# dcdc_60v_12v.net
KiCad netlist of a schematic drawn in Altium Designer
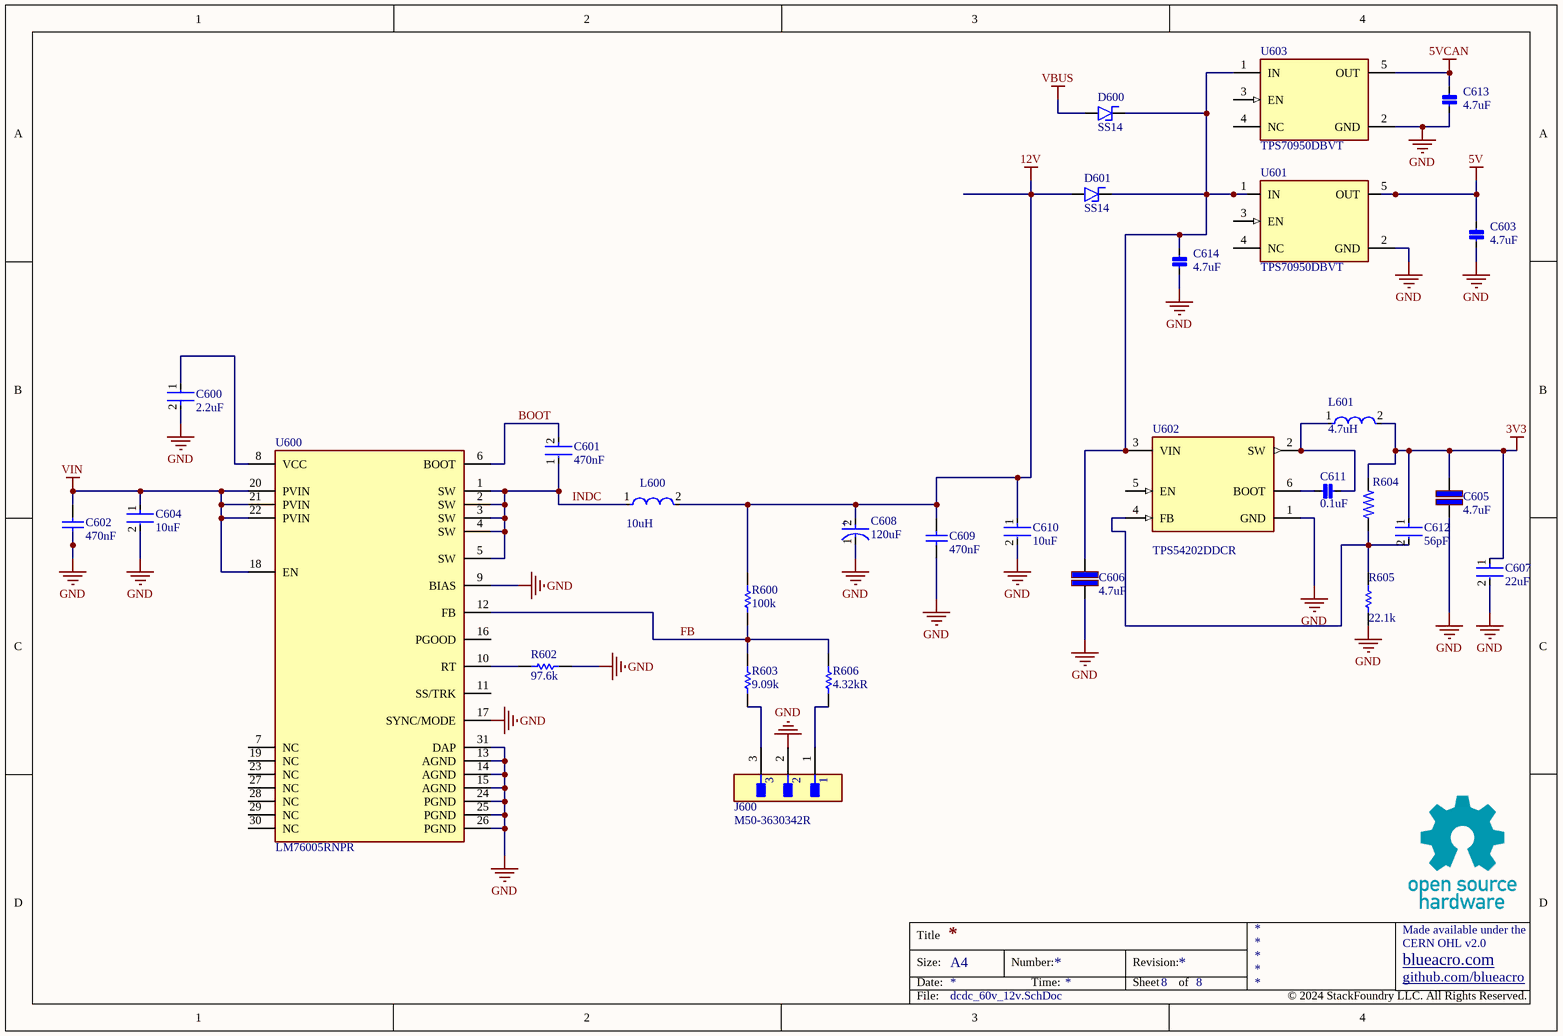
[diagram p0: dcdc_60v_12v.SchDoc]

(export (version "E")
  (design (tool "Eeschema 10.0.6"))
  (components
    (comp (ref "C600")
      (value "2.2uF")
      (footprint "FP-C1608-080-0_1-IPC_A")
      (description "Cap Ceramic 2.2uF 16V X6S 10% Pad SMD 0603 105°C Low ESR T/R")
      (fields (field (name "TOLERANCE") "10%") (field (name "Comment") "CAP 2.2uF 0603 16V X6S"))
      (libsource (lib "StackFoundry LLC") (part "236180d848d6139a670b325ea6854c9"))
    )
    (comp (ref "C601")
      (value "470nF")
      (footprint "FP-C1608-080-0_1-IPC_A")
      (description "Multilayer Ceramic Capacitor, 0.47 uF, 50 V, ± 10%, X7R, 0603 [1608 Metric]")
      (fields (field (name "TOLERANCE") "10%") (field (name "VOLTAGE") "50V"))
      (libsource (lib "StackFoundry LLC") (part "236180d848d6139a670b325ea6854c9"))
    )
    (comp (ref "C602")
      (value "470nF")
      (footprint "CAPC1210(3225)230_M")
      (description "Multilayer Ceramic Capacitor, 0.47 uF, 50 V, ± 10%, X7R, 1210 [3225 Metric]")
      (fields (field (name "TOLERANCE") "10%") (field (name "VOLTAGE") "50V"))
      (libsource (lib "StackFoundry LLC") (part "CAP"))
    )
    (comp (ref "C603")
      (value "4.7uF")
      (footprint "FP-CL10-IPC_C")
      (description "Cap Ceramic 4.7uF 6.3V X7R 10% SMD 0603 125°C Paper T/R")
      (fields (field (name "Comment") "CAP 4.7uF 0603 6.3V X7R"))
      (libsource (lib "StackFoundry LLC") (part "C-EU"))
    )
    (comp (ref "C604")
      (value "10uF")
      (footprint "FP-GRM32E-0_2-0_3-MFG")
      (description "Multilayer Ceramic Capacitors MLCC - SMD/SMT 1210 10uF 63volts *Derate Voltage/Temp")
      (fields (field (name "TOLERANCE") "10%") (field (name "VOLTAGE") "63V"))
      (libsource (lib "StackFoundry LLC") (part "11868f565c42a9108669ba33697ecf6"))
    )
    (comp (ref "C605")
      (value "4.7uF")
      (footprint "CAPC3225X20N")
      (description "CAP CER 4.7UF 50V X7R 1210")
      (fields (field (name "VOLTAGE") "50V") (field (name "TOLERANCE") "10%"))
      (libsource (lib "StackFoundry LLC") (part "4.7uF"))
    )
    (comp (ref "C606")
      (value "4.7uF")
      (footprint "CAPC3225X20N")
      (description "CAP CER 4.7UF 50V X7R 1210")
      (fields (field (name "VOLTAGE") "50V") (field (name "TOLERANCE") "10%"))
      (libsource (lib "StackFoundry LLC") (part "4.7uF"))
    )
    (comp (ref "C607")
      (value "22uF")
      (footprint "FP-1210-L_3_2_0_3-W_2_5_0-MFG")
      (description "1210 22 uF 25 V ±20% Tolerance X7R Multilayer Ceramic Chip Capacitor")
      (fields (field (name "TOLERANCE") "20%") (field (name "Comment") "CAP 22uF 25V 1210 X7R"))
      (libsource (lib "StackFoundry LLC") (part "02cd4be3c70576c341d710602a673aa"))
    )
    (comp (ref "C608")
      (value "120uF")
      (footprint "FP-OS-CON-SMT-F12-MFG")
      (description "Cap Aluminum Polymer 120uF 35VDC 20%( 10 X 12.6mm) SMD 0.018 Ohm 4400mA 5000h 105C T/R")
      (fields (field (name "VOLTAGE") "35V") (field (name "TOLERANCE") "20%"))
      (libsource (lib "StackFoundry LLC") (part "a7907c86e72a156c28511143de7831b"))
    )
    (comp (ref "C609")
      (value "470nF")
      (footprint "CAPC1210(3225)230_M")
      (description "Multilayer Ceramic Capacitor, 0.47 uF, 50 V, ± 10%, X7R, 1210 [3225 Metric]")
      (fields (field (name "TOLERANCE") "10%") (field (name "VOLTAGE") "50V"))
      (libsource (lib "StackFoundry LLC") (part "CAP"))
    )
    (comp (ref "C610")
      (value "10uF")
      (footprint "FP-GRM32E-0_2-0_3-MFG")
      (description "Multilayer Ceramic Capacitors MLCC - SMD/SMT 1210 10uF 63volts *Derate Voltage/Temp")
      (fields (field (name "TOLERANCE") "10%") (field (name "VOLTAGE") "63V"))
      (libsource (lib "StackFoundry LLC") (part "11868f565c42a9108669ba33697ecf6"))
    )
    (comp (ref "C611")
      (value "0.1uF")
      (footprint "FP-CL10-IPC_B")
      (description "Cap Ceramic 0.1uF 50V X7R 20% SMD 0603 125C Paper T/R")
      (fields (field (name "VOLTAGE") "50V") (field (name "Comment") "CAP 0.1uF 50V X7R 0603"))
      (libsource (lib "") (part "C-EU_1"))
    )
    (comp (ref "C612")
      (value "56pF")
      (footprint "FP-C0603C-CF-IPC_B")
      (description "Multilayer Ceramic Capacitor, 56 pF, 50 V, ± 5%, C0G (NP0), 0603 [1608 Metric]")
      (fields (field (name "TOLERANCE") "5%") (field (name "Comment") "C0603C560J5GACTU"))
      (libsource (lib "StackFoundry LLC") (part "b4654b650e69147ec39a6b967a45e02"))
    )
    (comp (ref "C613")
      (value "4.7uF")
      (footprint "FP-CL10-IPC_C")
      (description "Cap Ceramic 4.7uF 6.3V X7R 10% SMD 0603 125°C Paper T/R")
      (fields (field (name "Comment") "CAP 4.7uF 0603 6.3V X7R"))
      (libsource (lib "StackFoundry LLC") (part "C-EU"))
    )
    (comp (ref "C614")
      (value "4.7uF")
      (footprint "FP-CL10-IPC_C")
      (description "Cap Ceramic 4.7uF 6.3V X7R 10% SMD 0603 125°C Paper T/R")
      (fields (field (name "Comment") "CAP 4.7uF 0603 6.3V X7R"))
      (libsource (lib "StackFoundry LLC") (part "C-EU"))
    )
    (comp (ref "D600")
      (value "SS14")
      (footprint "SMA")
      (libsource (lib "StackFoundry LLC") (part "DIODE_SCHOTTKY"))
    )
    (comp (ref "D601")
      (value "SS14")
      (footprint "SMA")
      (libsource (lib "StackFoundry LLC") (part "DIODE_SCHOTTKY"))
    )
    (comp (ref "J600")
      (value "M50-3630342R")
      (footprint "FP-M50-3630342R-MFG")
      (description "3 Pos. Male SIL Vertical SMT Conn. RoHS Compliant: Yes")
      (libsource (lib "StackFoundry LLC") (part "0d3f023dd272f625e17a2be33dea85f"))
    )
    (comp (ref "L600")
      (value "10uH")
      (footprint "FP-IHLP-5050FD-FP_2_945x4-MFG")
      (description "Inductor Power Shielded Wirewound 10uH 20% 100KHz Powdered Iron 10A 17.2mOhm DCR 5050 T/R")
      (fields (field (name "TOLERANCE") "20%") (field (name "Comment") "IHLP5050FDER100M01"))
      (libsource (lib "StackFoundry LLC") (part "725321dda6339637d4d059423bc1c3c"))
    )
    (comp (ref "L601")
      (value "4.7uH")
      (footprint "FP-SRN4018-MFG")
      (description "Ind Power Semi-Shielded Wirewound 4.7uH 20% 100KHz Ferrite 1.9A 1515 T/R")
      (fields (field (name "TOLERANCE") "20%") (field (name "Comment") "SRN4018-4R7M"))
      (libsource (lib "StackFoundry LLC") (part "725321dda6339637d4d059423bc1c3c"))
    )
    (comp (ref "R600")
      (value "100k")
      (footprint "RESC1608-IPC-LL")
      (description "SMD Chip Resistor, 100 kOhm, ± 1%, 100 mW, 0603 [1608 Metric], Thick Film, General Purpose")
      (fields (field (name "TOLERANCE") "1%") (field (name "Comment") "100k 0603 1%"))
      (libsource (lib "StackFoundry LLC") (part "RES"))
    )
    (comp (ref "R602")
      (value "97.6k")
      (footprint "RESC1608-IPC-LL")
      (description "Res Thick Film 0603 97.6K Ohm 1% 1/10W ±100ppm/°C Molded SMD Paper T/R")
      (fields (field (name "TOLERANCE") "1%") (field (name "Comment") "97.6k 0603 1%"))
      (libsource (lib "StackFoundry LLC") (part "RES"))
    )
    (comp (ref "R603")
      (value "9.09k")
      (footprint "RESC1608-IPC-LL")
      (description "SMD Chip Resistor, 9.09 kOhm, ± 1%, 100 mW, 0603 [1608 Metric], Thick Film, General Purpose")
      (fields (field (name "Comment") "9.09k 0603 1%"))
      (libsource (lib "StackFoundry LLC") (part "RES"))
    )
    (comp (ref "R604")
      (value "100k 0603 1%")
      (footprint "RESC1608-IPC-LL")
      (description "Res Thick Film 1.6 x 0.8 mm 100K Ohm 1% 0.1W(1/10W) 100ppm/ C Molded SMD Paper T/R")
      (libsource (lib "StackFoundry LLC") (part "R-US"))
    )
    (comp (ref "R605")
      (value "22.1k")
      (footprint "RESC1608-IPC-LL")
      (description "RES SMD 22.1KOHM 0.1% 1/10W 0603")
      (fields (field (name "Comment") "22.1k 0603 0.1%"))
      (libsource (lib "StackFoundry LLC") (part "RES"))
    )
    (comp (ref "R606")
      (value "4.32kR")
      (footprint "RESC1608X55X30LL15T15")
      (description "SMD Chip Resistor, 4.32 kOhm, ± 1%, 100 mW, 0603 [1608 Metric], Thick Film, Precision")
      (fields (field (name "TOLERANCE") "1%") (field (name "Comment") "4.32k 0603 1%"))
      (libsource (lib "StackFoundry LLC") (part "RES"))
    )
    (comp (ref "U600")
      (value "LM76005RNPR")
      (footprint "FP-RNP0030A-MFG")
      (description "3.5-V to 60-V, 5-A synchronous step-down voltage converter 30-WQFN -40 to 125")
      (libsource (lib "StackFoundry LLC") (part "e2228dfeb00daf3b479f14d7f837c1f"))
    )
    (comp (ref "U601")
      (value "TPS70950DBVT")
      (footprint "FP-DBV0005A-IPC_B")
      (description "IC REG LINEAR 5V 150MA SOT23-5 / 150-mA, 30-V, UltraLow IQ, Low-Dropout Regulators with Enable")
      (libsource (lib "StackFoundry LLC") (part "07e51adf658dd7550fcbd1980b41b01"))
    )
    (comp (ref "U602")
      (value "TPS54202DDCR")
      (footprint "FP-DDC0006A-IPC_C")
      (libsource (lib "StackFoundry LLC") (part "35c2d3f1afc239a386b2ba50eead654"))
    )
    (comp (ref "U603")
      (value "TPS70950DBVT")
      (footprint "FP-DBV0005A-IPC_B")
      (description "IC REG LINEAR 5V 150MA SOT23-5 / 150-mA, 30-V, UltraLow IQ, Low-Dropout Regulators with Enable")
      (libsource (lib "StackFoundry LLC") (part "07e51adf658dd7550fcbd1980b41b01"))
    )
  )
  (nets
    (net (code "1") (name "/BOOT") (class "Default")
      (node (ref "C601") (pin "2") (pinfunction "2_2") (pintype "passive"))
      (node (ref "U600") (pin "6") (pinfunction "BOOT_6") (pintype "power_in"))
    )
    (net (code "2") (name "/FB") (class "Default")
      (node (ref "R600") (pin "1") (pinfunction "1_1") (pintype "passive"))
      (node (ref "R603") (pin "2") (pinfunction "2_2") (pintype "passive"))
      (node (ref "R606") (pin "2") (pinfunction "2_2") (pintype "passive"))
      (node (ref "U600") (pin "12") (pinfunction "FB_12") (pintype "passive"))
    )
    (net (code "3") (name "/INDC") (class "Default")
      (node (ref "C601") (pin "1") (pinfunction "1_1") (pintype "passive"))
      (node (ref "L600") (pin "1") (pinfunction "1_1") (pintype "passive"))
      (node (ref "U600") (pin "1") (pinfunction "SW_1") (pintype "power_in"))
      (node (ref "U600") (pin "2") (pinfunction "SW_2") (pintype "power_in"))
      (node (ref "U600") (pin "3") (pinfunction "SW_3") (pintype "power_in"))
      (node (ref "U600") (pin "4") (pinfunction "SW_4") (pintype "power_in"))
      (node (ref "U600") (pin "5") (pinfunction "SW_5") (pintype "power_in"))
    )
    (net (code "4") (name "3V3") (class "Default")
      (node (ref "C605") (pin "2") (pintype "passive"))
      (node (ref "C607") (pin "1") (pinfunction "1_1") (pintype "passive"))
      (node (ref "C612") (pin "1") (pinfunction "1_1") (pintype "passive"))
      (node (ref "L601") (pin "2") (pinfunction "2_2") (pintype "passive"))
      (node (ref "R604") (pin "2") (pinfunction "2_2") (pintype "passive"))
    )
    (net (code "5") (name "5V") (class "Default")
      (node (ref "C603") (pin "1") (pinfunction "1_1") (pintype "passive"))
      (node (ref "U601") (pin "5") (pinfunction "OUT_5") (pintype "passive"))
    )
    (net (code "6") (name "5VCAN") (class "Default")
      (node (ref "C613") (pin "1") (pinfunction "1_1") (pintype "passive"))
      (node (ref "U603") (pin "5") (pinfunction "OUT_5") (pintype "passive"))
    )
    (net (code "7") (name "12V") (class "Default")
      (node (ref "C608") (pin "2") (pinfunction "A_2") (pintype "passive"))
      (node (ref "C609") (pin "2") (pinfunction "2_2") (pintype "passive"))
      (node (ref "C610") (pin "1") (pinfunction "1_1") (pintype "passive"))
      (node (ref "D601") (pin "A") (pinfunction "A_A") (pintype "power_in"))
      (node (ref "L600") (pin "2") (pinfunction "2_2") (pintype "passive"))
      (node (ref "R600") (pin "2") (pinfunction "2_2") (pintype "passive"))
    )
    (net (code "8") (name "GND") (class "Default")
      (node (ref "C600") (pin "2") (pinfunction "2_2") (pintype "passive"))
      (node (ref "C602") (pin "1") (pinfunction "1_1") (pintype "passive"))
      (node (ref "C603") (pin "2") (pinfunction "2_2") (pintype "passive"))
      (node (ref "C604") (pin "2") (pinfunction "2_2") (pintype "passive"))
      (node (ref "C605") (pin "1") (pintype "passive"))
      (node (ref "C606") (pin "1") (pintype "passive"))
      (node (ref "C607") (pin "2") (pinfunction "2_2") (pintype "passive"))
      (node (ref "C608") (pin "1") (pinfunction "C_1") (pintype "passive"))
      (node (ref "C609") (pin "1") (pinfunction "1_1") (pintype "passive"))
      (node (ref "C610") (pin "2") (pinfunction "2_2") (pintype "passive"))
      (node (ref "C613") (pin "2") (pinfunction "2_2") (pintype "passive"))
      (node (ref "C614") (pin "2") (pinfunction "2_2") (pintype "passive"))
      (node (ref "J600") (pin "2") (pinfunction "2_2") (pintype "passive"))
      (node (ref "R602") (pin "2") (pinfunction "2_2") (pintype "passive"))
      (node (ref "R605") (pin "1") (pinfunction "1_1") (pintype "passive"))
      (node (ref "U600") (pin "13") (pinfunction "AGND_13") (pintype "power_in"))
      (node (ref "U600") (pin "14") (pinfunction "AGND_14") (pintype "power_in"))
      (node (ref "U600") (pin "15") (pinfunction "AGND_15") (pintype "power_in"))
      (node (ref "U600") (pin "17") (pinfunction "SYNC/MODE_17") (pintype "passive"))
      (node (ref "U600") (pin "24") (pinfunction "PGND_24") (pintype "power_in"))
      (node (ref "U600") (pin "25") (pinfunction "PGND_25") (pintype "power_in"))
      (node (ref "U600") (pin "26") (pinfunction "PGND_26") (pintype "power_in"))
      (node (ref "U600") (pin "31") (pinfunction "DAP_31") (pintype "power_in"))
      (node (ref "U600") (pin "9") (pinfunction "BIAS_9") (pintype "power_in"))
      (node (ref "U601") (pin "2") (pinfunction "GND_2") (pintype "power_in"))
      (node (ref "U602") (pin "1") (pinfunction "GND_1") (pintype "power_in"))
      (node (ref "U603") (pin "2") (pinfunction "GND_2") (pintype "power_in"))
    )
    (net (code "9") (name "Net-(J600-Pad1)") (class "Default")
      (node (ref "J600") (pin "1") (pinfunction "1_1") (pintype "passive"))
      (node (ref "R606") (pin "1") (pinfunction "1_1") (pintype "passive"))
    )
    (net (code "10") (name "Net-(J600-Pad3)") (class "Default")
      (node (ref "J600") (pin "3") (pinfunction "3_3") (pintype "passive"))
      (node (ref "R603") (pin "1") (pinfunction "1_1") (pintype "passive"))
    )
    (net (code "11") (name "Net-(U600-RT)") (class "Default")
      (node (ref "R602") (pin "1") (pinfunction "1_1") (pintype "passive"))
      (node (ref "U600") (pin "10") (pinfunction "RT_10") (pintype "passive"))
    )
    (net (code "12") (name "Net-(U600-VCC)") (class "Default")
      (node (ref "C600") (pin "1") (pinfunction "1_1") (pintype "passive"))
      (node (ref "U600") (pin "8") (pinfunction "VCC_8") (pintype "power_in"))
    )
    (net (code "13") (name "Net-(U601-IN)") (class "Default")
      (node (ref "C606") (pin "2") (pintype "passive"))
      (node (ref "C614") (pin "1") (pinfunction "1_1") (pintype "passive"))
      (node (ref "D600") (pin "K") (pinfunction "K_K") (pintype "power_in"))
      (node (ref "D601") (pin "K") (pinfunction "K_K") (pintype "power_in"))
      (node (ref "U601") (pin "1") (pinfunction "IN_1") (pintype "power_in"))
      (node (ref "U602") (pin "3") (pinfunction "VIN_3") (pintype "power_in"))
      (node (ref "U603") (pin "1") (pinfunction "IN_1") (pintype "power_in"))
    )
    (net (code "14") (name "Net-(U602-BOOT)") (class "Default")
      (node (ref "C611") (pin "1") (pinfunction "1_1") (pintype "passive"))
      (node (ref "U602") (pin "6") (pinfunction "BOOT_6") (pintype "passive"))
    )
    (net (code "15") (name "Net-(U602-FB)") (class "Default")
      (node (ref "C612") (pin "2") (pinfunction "2_2") (pintype "passive"))
      (node (ref "R604") (pin "1") (pinfunction "1_1") (pintype "passive"))
      (node (ref "R605") (pin "2") (pinfunction "2_2") (pintype "passive"))
      (node (ref "U602") (pin "4") (pinfunction "FB_4") (pintype "input"))
    )
    (net (code "16") (name "Net-(U602-SW)") (class "Default")
      (node (ref "C611") (pin "2") (pinfunction "2_2") (pintype "passive"))
      (node (ref "L601") (pin "1") (pinfunction "1_1") (pintype "passive"))
      (node (ref "U602") (pin "2") (pinfunction "SW_2") (pintype "output"))
    )
    (net (code "17") (name "VBUS") (class "Default")
      (node (ref "D600") (pin "A") (pinfunction "A_A") (pintype "power_in"))
    )
    (net (code "18") (name "VIN") (class "Default")
      (node (ref "C602") (pin "2") (pinfunction "2_2") (pintype "passive"))
      (node (ref "C604") (pin "1") (pinfunction "1_1") (pintype "passive"))
      (node (ref "U600") (pin "18") (pinfunction "EN_18") (pintype "passive"))
      (node (ref "U600") (pin "20") (pinfunction "PVIN_20") (pintype "power_in"))
      (node (ref "U600") (pin "21") (pinfunction "PVIN_21") (pintype "power_in"))
      (node (ref "U600") (pin "22") (pinfunction "PVIN_22") (pintype "power_in"))
    )
    (net (code "19") (name "unconnected-(U600-NC-Pad7)") (class "Default")
      (node (ref "U600") (pin "7") (pinfunction "NC_7") (pintype "passive"))
    )
    (net (code "20") (name "unconnected-(U600-NC-Pad19)") (class "Default")
      (node (ref "U600") (pin "19") (pinfunction "NC_19") (pintype "passive"))
    )
    (net (code "21") (name "unconnected-(U600-NC-Pad23)") (class "Default")
      (node (ref "U600") (pin "23") (pinfunction "NC_23") (pintype "passive"))
    )
    (net (code "22") (name "unconnected-(U600-NC-Pad27)") (class "Default")
      (node (ref "U600") (pin "27") (pinfunction "NC_27") (pintype "passive"))
    )
    (net (code "23") (name "unconnected-(U600-NC-Pad28)") (class "Default")
      (node (ref "U600") (pin "28") (pinfunction "NC_28") (pintype "passive"))
    )
    (net (code "24") (name "unconnected-(U600-NC-Pad29)") (class "Default")
      (node (ref "U600") (pin "29") (pinfunction "NC_29") (pintype "passive"))
    )
    (net (code "25") (name "unconnected-(U600-NC-Pad30)") (class "Default")
      (node (ref "U600") (pin "30") (pinfunction "NC_30") (pintype "passive"))
    )
    (net (code "26") (name "unconnected-(U600-PGOOD-Pad16)") (class "Default")
      (node (ref "U600") (pin "16") (pinfunction "PGOOD_16") (pintype "open_collector"))
    )
    (net (code "27") (name "unconnected-(U600-SS{slash}TRK-Pad11)") (class "Default")
      (node (ref "U600") (pin "11") (pinfunction "SS/TRK_11") (pintype "passive"))
    )
    (net (code "28") (name "unconnected-(U601-EN-Pad3)") (class "Default")
      (node (ref "U601") (pin "3") (pinfunction "EN_3") (pintype "input"))
    )
    (net (code "29") (name "unconnected-(U601-NC-Pad4)") (class "Default")
      (node (ref "U601") (pin "4") (pinfunction "NC_4") (pintype "passive"))
    )
    (net (code "30") (name "unconnected-(U602-EN-Pad5)") (class "Default")
      (node (ref "U602") (pin "5") (pinfunction "EN_5") (pintype "input"))
    )
    (net (code "31") (name "unconnected-(U603-EN-Pad3)") (class "Default")
      (node (ref "U603") (pin "3") (pinfunction "EN_3") (pintype "input"))
    )
    (net (code "32") (name "unconnected-(U603-NC-Pad4)") (class "Default")
      (node (ref "U603") (pin "4") (pinfunction "NC_4") (pintype "passive"))
    )
  )
)
